# Microcontroller.net
KiCad netlist of a schematic drawn in Altium Designer
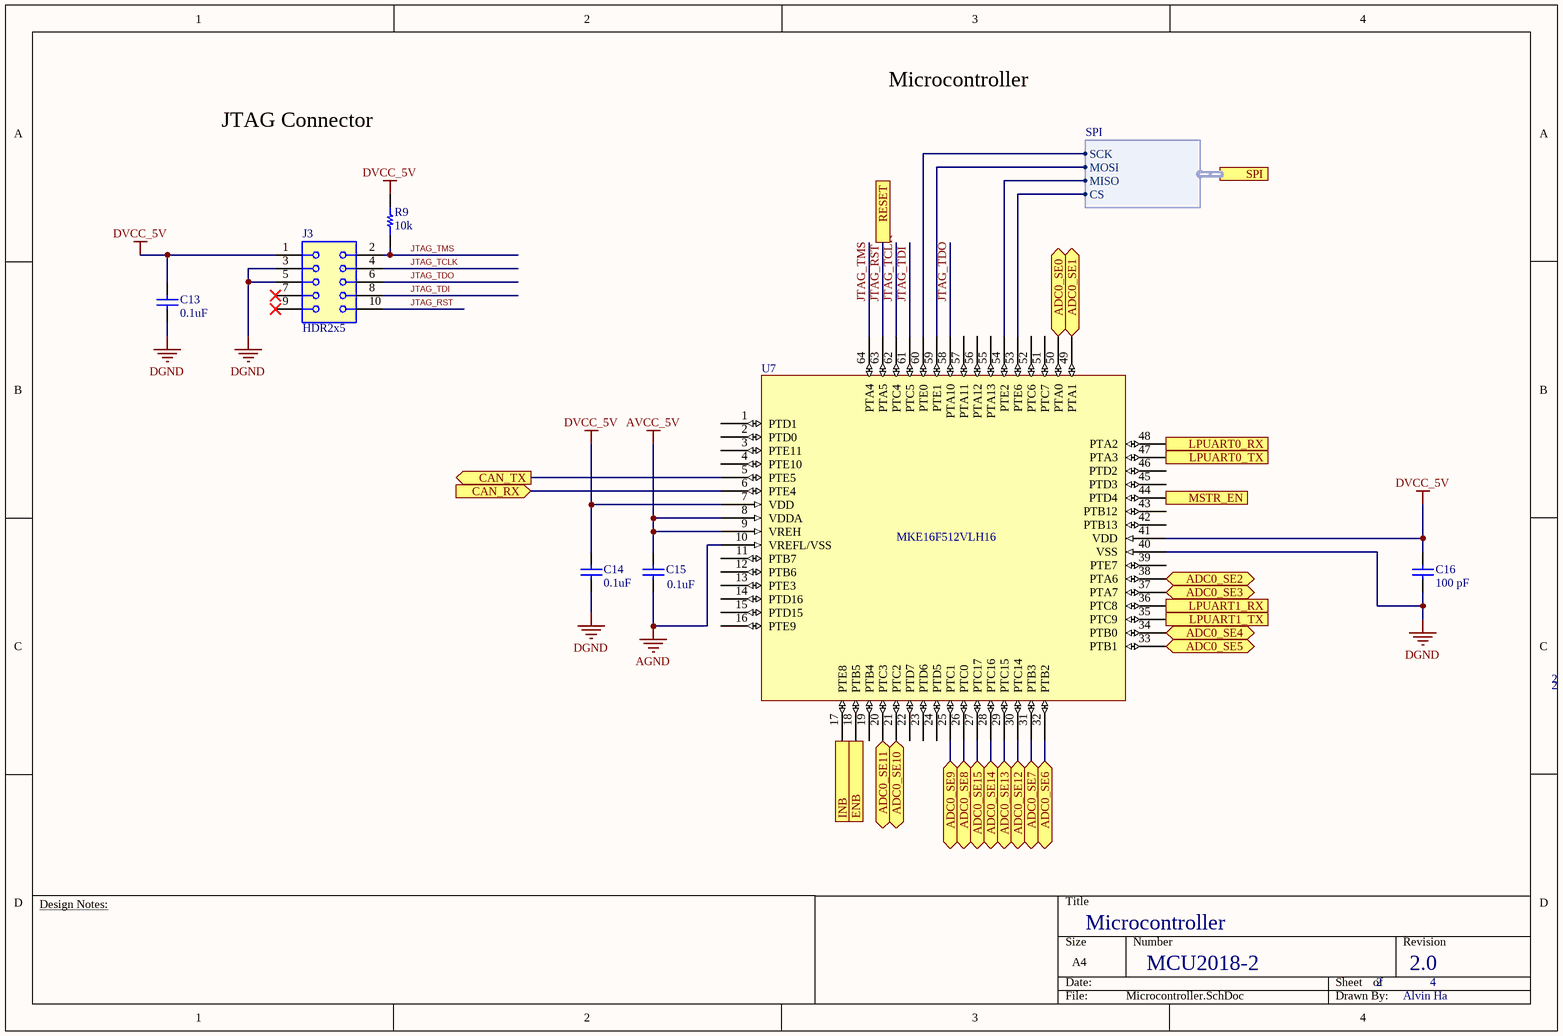
[diagram p0: Microcontroller.SchDoc]

(export (version "E")
  (design (tool "Eeschema 10.0.6"))
  (components
    (comp (ref "C13")
      (value "0.1uF")
      (footprint "CAP SMT 0603")
      (libsource (lib "Components") (part "Capacitor 0.1uF 25V 0603"))
    )
    (comp (ref "C14")
      (value "0.1uF")
      (footprint "CAP SMT 0603")
      (libsource (lib "Components") (part "Capacitor 0.1uF 25V 0603"))
    )
    (comp (ref "C15")
      (value "0.1uF")
      (footprint "CAP SMT 0603")
      (libsource (lib "Components") (part "Capacitor 0.1uF 25V 0603"))
    )
    (comp (ref "C16")
      (value "100 pF")
      (footprint "CAP SMT 0603")
      (libsource (lib "Components") (part "Capacitor 100 pF 25V 0603"))
    )
    (comp (ref "J3") (value "HDR2x5") (footprint "HDR 2x5") (libsource (lib "Components") (part "HDR2x5")))
    (comp (ref "R9")
      (value "10k")
      (footprint "RES SMT 0805")
      (libsource (lib "Components") (part "Resistor 10k 1% 0805"))
    )
    (comp (ref "U7")
      (value "MKE16F512VLH16")
      (footprint "MKE16F512VLH16")
      (libsource (lib "BMS_Library") (part "MKE16F512VLH16"))
    )
  )
  (nets
    (net (code "2") (name "/ADC0_SE0") (class "Default")
      (node (ref "U7") (pin "50") (pinfunction "PTA0_50") (pintype "bidirectional"))
    )
    (net (code "3") (name "/ADC0_SE1") (class "Default")
      (node (ref "U7") (pin "49") (pinfunction "PTA1_49") (pintype "bidirectional"))
    )
    (net (code "4") (name "/ADC0_SE2") (class "Default")
      (node (ref "U7") (pin "38") (pinfunction "PTA6_38") (pintype "bidirectional"))
    )
    (net (code "5") (name "/ADC0_SE3") (class "Default")
      (node (ref "U7") (pin "37") (pinfunction "PTA7_37") (pintype "bidirectional"))
    )
    (net (code "6") (name "/ADC0_SE4") (class "Default")
      (node (ref "U7") (pin "34") (pinfunction "PTB0_34") (pintype "bidirectional"))
    )
    (net (code "7") (name "/ADC0_SE5") (class "Default")
      (node (ref "U7") (pin "33") (pinfunction "PTB1_33") (pintype "bidirectional"))
    )
    (net (code "8") (name "/ADC0_SE6") (class "Default")
      (node (ref "U7") (pin "32") (pinfunction "PTB2_32") (pintype "bidirectional"))
    )
    (net (code "9") (name "/ADC0_SE7") (class "Default")
      (node (ref "U7") (pin "31") (pinfunction "PTB3_31") (pintype "bidirectional"))
    )
    (net (code "10") (name "/ADC0_SE8") (class "Default")
      (node (ref "U7") (pin "26") (pinfunction "PTC0_26") (pintype "bidirectional"))
    )
    (net (code "11") (name "/ADC0_SE9") (class "Default")
      (node (ref "U7") (pin "25") (pinfunction "PTC1_25") (pintype "bidirectional"))
    )
    (net (code "12") (name "/ADC0_SE10") (class "Default")
      (node (ref "U7") (pin "21") (pinfunction "PTC2_21") (pintype "bidirectional"))
    )
    (net (code "13") (name "/ADC0_SE11") (class "Default")
      (node (ref "U7") (pin "20") (pinfunction "PTC3_20") (pintype "bidirectional"))
    )
    (net (code "14") (name "/ADC0_SE12") (class "Default")
      (node (ref "U7") (pin "30") (pinfunction "PTC14_30") (pintype "bidirectional"))
    )
    (net (code "15") (name "/ADC0_SE13") (class "Default")
      (node (ref "U7") (pin "29") (pinfunction "PTC15_29") (pintype "bidirectional"))
    )
    (net (code "16") (name "/ADC0_SE14") (class "Default")
      (node (ref "U7") (pin "28") (pinfunction "PTC16_28") (pintype "bidirectional"))
    )
    (net (code "17") (name "/ADC0_SE15") (class "Default")
      (node (ref "U7") (pin "27") (pinfunction "PTC17_27") (pintype "bidirectional"))
    )
    (net (code "18") (name "/CAN_RX") (class "Default")
      (node (ref "U7") (pin "6") (pinfunction "PTE4_6") (pintype "bidirectional"))
    )
    (net (code "19") (name "/CAN_TX") (class "Default")
      (node (ref "U7") (pin "5") (pinfunction "PTE5_5") (pintype "bidirectional"))
    )
    (net (code "20") (name "/CS") (class "Default")
      (node (ref "U7") (pin "53") (pinfunction "PTE6_53") (pintype "bidirectional"))
    )
    (net (code "21") (name "/ENB") (class "Default")
      (node (ref "U7") (pin "18") (pinfunction "PTB5_18") (pintype "bidirectional"))
    )
    (net (code "22") (name "/INB") (class "Default")
      (node (ref "U7") (pin "17") (pinfunction "PTE8_17") (pintype "bidirectional"))
    )
    (net (code "23") (name "/JTAG_RST") (class "Default")
      (node (ref "J3") (pin "10") (pinfunction "10_10") (pintype "passive"))
      (node (ref "U7") (pin "63") (pinfunction "PTA5_63") (pintype "bidirectional"))
    )
    (net (code "24") (name "/JTAG_TCLK") (class "Default")
      (node (ref "J3") (pin "4") (pinfunction "4_4") (pintype "passive"))
      (node (ref "U7") (pin "62") (pinfunction "PTC4_62") (pintype "bidirectional"))
    )
    (net (code "25") (name "/JTAG_TDI") (class "Default")
      (node (ref "J3") (pin "8") (pinfunction "8_8") (pintype "passive"))
      (node (ref "U7") (pin "61") (pinfunction "PTC5_61") (pintype "bidirectional"))
    )
    (net (code "26") (name "/JTAG_TDO") (class "Default")
      (node (ref "J3") (pin "6") (pinfunction "6_6") (pintype "passive"))
      (node (ref "U7") (pin "58") (pinfunction "PTA10_58") (pintype "bidirectional"))
    )
    (net (code "27") (name "/JTAG_TMS") (class "Default")
      (node (ref "J3") (pin "2") (pinfunction "2_2") (pintype "passive"))
      (node (ref "R9") (pin "1") (pinfunction "1_1") (pintype "passive"))
      (node (ref "U7") (pin "64") (pinfunction "PTA4_64") (pintype "bidirectional"))
    )
    (net (code "28") (name "/LPUART0_RX") (class "Default")
      (node (ref "U7") (pin "48") (pinfunction "PTA2_48") (pintype "bidirectional"))
    )
    (net (code "29") (name "/LPUART0_TX") (class "Default")
      (node (ref "U7") (pin "47") (pinfunction "PTA3_47") (pintype "bidirectional"))
    )
    (net (code "30") (name "/LPUART1_RX") (class "Default")
      (node (ref "U7") (pin "36") (pinfunction "PTC8_36") (pintype "bidirectional"))
    )
    (net (code "31") (name "/LPUART1_TX") (class "Default")
      (node (ref "U7") (pin "35") (pinfunction "PTC9_35") (pintype "bidirectional"))
    )
    (net (code "32") (name "/MISO") (class "Default")
      (node (ref "U7") (pin "54") (pinfunction "PTE2_54") (pintype "bidirectional"))
    )
    (net (code "33") (name "/MOSI") (class "Default")
      (node (ref "U7") (pin "59") (pinfunction "PTE1_59") (pintype "bidirectional"))
    )
    (net (code "34") (name "/MSTR_EN") (class "Default")
      (node (ref "U7") (pin "44") (pinfunction "PTD4_44") (pintype "bidirectional"))
    )
    (net (code "35") (name "/SCK") (class "Default")
      (node (ref "U7") (pin "60") (pinfunction "PTE0_60") (pintype "bidirectional"))
    )
    (net (code "37") (name "AGND") (class "Default")
      (node (ref "C15") (pin "1") (pinfunction "1_1") (pintype "passive"))
      (node (ref "U7") (pin "10") (pinfunction "VREFL/VSS_10") (pintype "input"))
    )
    (net (code "38") (name "AVCC_5V") (class "Default")
      (node (ref "C15") (pin "2") (pinfunction "2_2") (pintype "passive"))
      (node (ref "U7") (pin "8") (pinfunction "VDDA_8") (pintype "input"))
      (node (ref "U7") (pin "9") (pinfunction "VREH_9") (pintype "input"))
    )
    (net (code "39") (name "DGND") (class "Default")
      (node (ref "C13") (pin "1") (pinfunction "1_1") (pintype "passive"))
      (node (ref "C14") (pin "1") (pinfunction "1_1") (pintype "passive"))
      (node (ref "C16") (pin "1") (pinfunction "1_1") (pintype "passive"))
      (node (ref "J3") (pin "3") (pinfunction "3_3") (pintype "passive"))
      (node (ref "J3") (pin "5") (pinfunction "5_5") (pintype "passive"))
      (node (ref "U7") (pin "40") (pinfunction "VSS_40") (pintype "input"))
    )
    (net (code "40") (name "DVCC_5V") (class "Default")
      (node (ref "C13") (pin "2") (pinfunction "2_2") (pintype "passive"))
      (node (ref "C14") (pin "2") (pinfunction "2_2") (pintype "passive"))
      (node (ref "C16") (pin "2") (pinfunction "2_2") (pintype "passive"))
      (node (ref "J3") (pin "1") (pinfunction "1_1") (pintype "passive"))
      (node (ref "R9") (pin "2") (pinfunction "2_2") (pintype "passive"))
      (node (ref "U7") (pin "41") (pinfunction "VDD_41") (pintype "input"))
      (node (ref "U7") (pin "7") (pinfunction "VDD_7") (pintype "input"))
    )
    (net (code "41") (name "unconnected-(J3-Pad7)") (class "Default")
      (node (ref "J3") (pin "7") (pinfunction "7_7") (pintype "passive+no_connect"))
    )
    (net (code "42") (name "unconnected-(J3-Pad9)") (class "Default")
      (node (ref "J3") (pin "9") (pinfunction "9_9") (pintype "passive+no_connect"))
    )
    (net (code "43") (name "unconnected-(U7-PTA11-Pad57)") (class "Default")
      (node (ref "U7") (pin "57") (pinfunction "PTA11_57") (pintype "bidirectional"))
    )
    (net (code "44") (name "unconnected-(U7-PTA12-Pad56)") (class "Default")
      (node (ref "U7") (pin "56") (pinfunction "PTA12_56") (pintype "bidirectional"))
    )
    (net (code "45") (name "unconnected-(U7-PTA13-Pad55)") (class "Default")
      (node (ref "U7") (pin "55") (pinfunction "PTA13_55") (pintype "bidirectional"))
    )
    (net (code "46") (name "unconnected-(U7-PTB4-Pad19)") (class "Default")
      (node (ref "U7") (pin "19") (pinfunction "PTB4_19") (pintype "bidirectional"))
    )
    (net (code "47") (name "unconnected-(U7-PTB6-Pad12)") (class "Default")
      (node (ref "U7") (pin "12") (pinfunction "PTB6_12") (pintype "bidirectional"))
    )
    (net (code "48") (name "unconnected-(U7-PTB7-Pad11)") (class "Default")
      (node (ref "U7") (pin "11") (pinfunction "PTB7_11") (pintype "bidirectional"))
    )
    (net (code "49") (name "unconnected-(U7-PTB12-Pad43)") (class "Default")
      (node (ref "U7") (pin "43") (pinfunction "PTB12_43") (pintype "bidirectional"))
    )
    (net (code "50") (name "unconnected-(U7-PTB13-Pad42)") (class "Default")
      (node (ref "U7") (pin "42") (pinfunction "PTB13_42") (pintype "bidirectional"))
    )
    (net (code "51") (name "unconnected-(U7-PTC6-Pad52)") (class "Default")
      (node (ref "U7") (pin "52") (pinfunction "PTC6_52") (pintype "bidirectional"))
    )
    (net (code "52") (name "unconnected-(U7-PTC7-Pad51)") (class "Default")
      (node (ref "U7") (pin "51") (pinfunction "PTC7_51") (pintype "bidirectional"))
    )
    (net (code "53") (name "unconnected-(U7-PTD0-Pad2)") (class "Default")
      (node (ref "U7") (pin "2") (pinfunction "PTD0_2") (pintype "bidirectional"))
    )
    (net (code "54") (name "unconnected-(U7-PTD1-Pad1)") (class "Default")
      (node (ref "U7") (pin "1") (pinfunction "PTD1_1") (pintype "bidirectional"))
    )
    (net (code "55") (name "unconnected-(U7-PTD2-Pad46)") (class "Default")
      (node (ref "U7") (pin "46") (pinfunction "PTD2_46") (pintype "bidirectional"))
    )
    (net (code "56") (name "unconnected-(U7-PTD3-Pad45)") (class "Default")
      (node (ref "U7") (pin "45") (pinfunction "PTD3_45") (pintype "bidirectional"))
    )
    (net (code "57") (name "unconnected-(U7-PTD5-Pad24)") (class "Default")
      (node (ref "U7") (pin "24") (pinfunction "PTD5_24") (pintype "bidirectional"))
    )
    (net (code "58") (name "unconnected-(U7-PTD6-Pad23)") (class "Default")
      (node (ref "U7") (pin "23") (pinfunction "PTD6_23") (pintype "bidirectional"))
    )
    (net (code "59") (name "unconnected-(U7-PTD7-Pad22)") (class "Default")
      (node (ref "U7") (pin "22") (pinfunction "PTD7_22") (pintype "bidirectional"))
    )
    (net (code "60") (name "unconnected-(U7-PTD15-Pad15)") (class "Default")
      (node (ref "U7") (pin "15") (pinfunction "PTD15_15") (pintype "bidirectional"))
    )
    (net (code "61") (name "unconnected-(U7-PTD16-Pad14)") (class "Default")
      (node (ref "U7") (pin "14") (pinfunction "PTD16_14") (pintype "bidirectional"))
    )
    (net (code "62") (name "unconnected-(U7-PTE3-Pad13)") (class "Default")
      (node (ref "U7") (pin "13") (pinfunction "PTE3_13") (pintype "bidirectional"))
    )
    (net (code "63") (name "unconnected-(U7-PTE7-Pad39)") (class "Default")
      (node (ref "U7") (pin "39") (pinfunction "PTE7_39") (pintype "bidirectional"))
    )
    (net (code "64") (name "unconnected-(U7-PTE9-Pad16)") (class "Default")
      (node (ref "U7") (pin "16") (pinfunction "PTE9_16") (pintype "bidirectional"))
    )
    (net (code "65") (name "unconnected-(U7-PTE10-Pad4)") (class "Default")
      (node (ref "U7") (pin "4") (pinfunction "PTE10_4") (pintype "bidirectional"))
    )
    (net (code "66") (name "unconnected-(U7-PTE11-Pad3)") (class "Default")
      (node (ref "U7") (pin "3") (pinfunction "PTE11_3") (pintype "bidirectional"))
    )
  )
)
